# Ground_Station_2019-2020.net
KiCad netlist of a schematic drawn in EAGLE
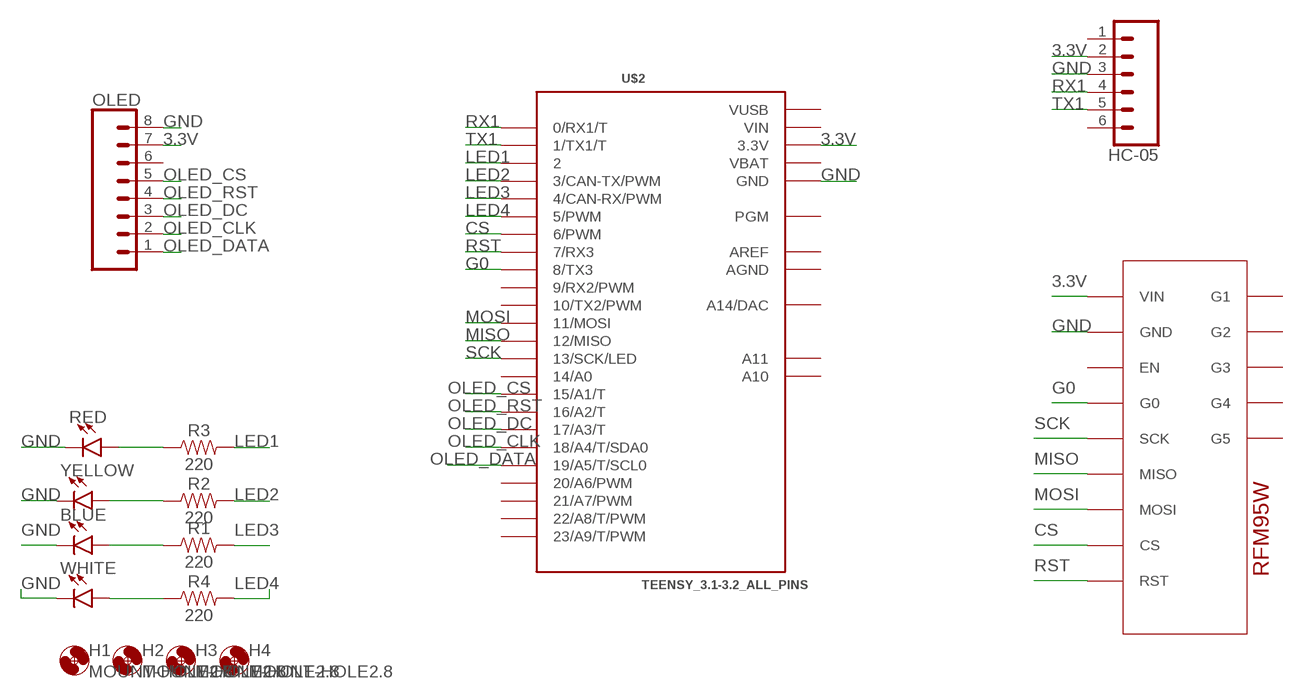
[diagram p0: schematic, sheet 1]

(export (version "E")
  (design (tool "Eeschema 10.0.6"))
  (components
    (comp (ref "BLUE")
      (value "LED5MM")
      (footprint "eagle-import:LED_5MM")
      (libsource (lib "eagle-import") (part "LED5MM"))
    )
    (comp (ref "H1")
      (value "MOUNT-HOLE2.8")
      (footprint "eagle-import:2,8")
      (libsource (lib "eagle-import") (part "MOUNT-HOLE2.8"))
    )
    (comp (ref "H2")
      (value "MOUNT-HOLE2.8")
      (footprint "eagle-import:2,8")
      (libsource (lib "eagle-import") (part "MOUNT-HOLE2.8"))
    )
    (comp (ref "H3")
      (value "MOUNT-HOLE2.8")
      (footprint "eagle-import:2,8")
      (libsource (lib "eagle-import") (part "MOUNT-HOLE2.8"))
    )
    (comp (ref "H4")
      (value "MOUNT-HOLE2.8")
      (footprint "eagle-import:2,8")
      (libsource (lib "eagle-import") (part "MOUNT-HOLE2.8"))
    )
    (comp (ref "HC-05")
      (value "CONN_06SILK_FEMALE_PTH")
      (footprint "eagle-import:1X06")
      (libsource (lib "eagle-import") (part "CONN_06SILK_FEMALE_PTH"))
    )
    (comp (ref "OLED")
      (value "CONN_08\"")
      (footprint "eagle-import:1X08")
      (libsource (lib "eagle-import") (part "CONN_08{dblquote}"))
    )
    (comp (ref "R1")
      (value "220")
      (footprint "eagle-import:AXIAL-0.3")
      (libsource (lib "eagle-import") (part "330OHM-HORIZ-1/10W-5%"))
    )
    (comp (ref "R2")
      (value "220")
      (footprint "eagle-import:AXIAL-0.3")
      (libsource (lib "eagle-import") (part "330OHM-HORIZ-1/10W-5%"))
    )
    (comp (ref "R3")
      (value "220")
      (footprint "eagle-import:AXIAL-0.3")
      (libsource (lib "eagle-import") (part "330OHM-HORIZ-1/10W-5%"))
    )
    (comp (ref "R4")
      (value "220")
      (footprint "eagle-import:AXIAL-0.3")
      (libsource (lib "eagle-import") (part "330OHM-HORIZ-1/10W-5%"))
    )
    (comp (ref "RED")
      (value "LED5MM")
      (footprint "eagle-import:LED_5MM")
      (libsource (lib "eagle-import") (part "LED5MM"))
    )
    (comp (ref "U$2")
      (value "TEENSY_3.1-3.2_ALL_PINS")
      (footprint "eagle-import:TEENSY_3.0-3.2&LC_ALL_PINS")
      (libsource (lib "eagle-import") (part "TEENSY_3.1-3.2_ALL_PINS"))
    )
    (comp (ref "U1")
      (value "ADAFRUIT_RFM95W_LORA_RADIO")
      (footprint "eagle-import:ADAFRUIT_RFM95W_LORA_RADIO")
      (libsource (lib "eagle-import") (part "ADAFRUIT_RFM95W_LORA_RADIO"))
    )
    (comp (ref "WHITE")
      (value "LED5MM")
      (footprint "eagle-import:LED_5MM")
      (libsource (lib "eagle-import") (part "LED5MM"))
    )
    (comp (ref "YELLOW")
      (value "LED5MM")
      (footprint "eagle-import:LED_5MM")
      (libsource (lib "eagle-import") (part "LED5MM"))
    )
  )
  (nets
    (net (code "1") (name "/3.3V") (class "Default")
      (node (ref "HC-05") (pin "2") (pinfunction "2_2") (pintype "passive"))
      (node (ref "OLED") (pin "7") (pinfunction "7_7") (pintype "passive"))
      (node (ref "U$2") (pin "3.3V") (pinfunction "3.3V_3.3V") (pintype "power_in"))
      (node (ref "U$2") (pin "3.3V1") (pinfunction "3.3V_3.3V1") (pintype "power_in"))
      (node (ref "U1") (pin "1") (pinfunction "VIN_1") (pintype "bidirectional"))
    )
    (net (code "2") (name "/AGND") (class "Default")
      (node (ref "U$2") (pin "AGND") (pinfunction "AGND_AGND") (pintype "power_in"))
    )
    (net (code "3") (name "/AREF") (class "Default")
      (node (ref "U$2") (pin "AREF") (pinfunction "AREF_AREF") (pintype "power_in"))
    )
    (net (code "4") (name "/CS") (class "Default")
      (node (ref "U$2") (pin "6") (pinfunction "6/PWM_6") (pintype "bidirectional"))
      (node (ref "U1") (pin "8") (pinfunction "CS_8") (pintype "bidirectional"))
    )
    (net (code "5") (name "/G0") (class "Default")
      (node (ref "U$2") (pin "8") (pinfunction "8/TX3_8") (pintype "bidirectional"))
      (node (ref "U1") (pin "4") (pinfunction "G0_4") (pintype "bidirectional"))
    )
    (net (code "6") (name "/GND") (class "Default")
      (node (ref "BLUE") (pin "K") (pinfunction "C_K") (pintype "passive"))
      (node (ref "HC-05") (pin "3") (pinfunction "3_3") (pintype "passive"))
      (node (ref "OLED") (pin "8") (pinfunction "8_8") (pintype "passive"))
      (node (ref "RED") (pin "K") (pinfunction "C_K") (pintype "passive"))
      (node (ref "U$2") (pin "GND") (pinfunction "GND_GND") (pintype "power_in"))
      (node (ref "U$2") (pin "GND1") (pinfunction "GND_GND1") (pintype "power_in"))
      (node (ref "U1") (pin "2") (pinfunction "GND_2") (pintype "bidirectional"))
      (node (ref "WHITE") (pin "K") (pinfunction "C_K") (pintype "passive"))
      (node (ref "YELLOW") (pin "K") (pinfunction "C_K") (pintype "passive"))
    )
    (net (code "7") (name "/LED1") (class "Default")
      (node (ref "R3") (pin "P$2") (pinfunction "2_P$2") (pintype "passive"))
      (node (ref "U$2") (pin "2") (pinfunction "2_2") (pintype "bidirectional"))
    )
    (net (code "8") (name "/LED2") (class "Default")
      (node (ref "R2") (pin "P$2") (pinfunction "2_P$2") (pintype "passive"))
      (node (ref "U$2") (pin "3") (pinfunction "3/CAN-TX/PWM_3") (pintype "bidirectional"))
    )
    (net (code "9") (name "/LED3") (class "Default")
      (node (ref "R1") (pin "P$2") (pinfunction "2_P$2") (pintype "passive"))
      (node (ref "U$2") (pin "4") (pinfunction "4/CAN-RX/PWM_4") (pintype "bidirectional"))
    )
    (net (code "10") (name "/LED4") (class "Default")
      (node (ref "R4") (pin "P$2") (pinfunction "2_P$2") (pintype "passive"))
      (node (ref "U$2") (pin "5") (pinfunction "5/PWM_5") (pintype "bidirectional"))
    )
    (net (code "11") (name "/MISO") (class "Default")
      (node (ref "U$2") (pin "12") (pinfunction "12/MISO_12") (pintype "bidirectional"))
      (node (ref "U1") (pin "6") (pinfunction "MISO_6") (pintype "bidirectional"))
    )
    (net (code "12") (name "/MOSI") (class "Default")
      (node (ref "U$2") (pin "11") (pinfunction "11/MOSI_11") (pintype "bidirectional"))
      (node (ref "U1") (pin "7") (pinfunction "MOSI_7") (pintype "bidirectional"))
    )
    (net (code "13") (name "/OLED_CLK") (class "Default")
      (node (ref "OLED") (pin "2") (pinfunction "2_2") (pintype "passive"))
      (node (ref "U$2") (pin "18/A4") (pinfunction "18/A4/T/SDA0_18/A4") (pintype "bidirectional"))
    )
    (net (code "14") (name "/OLED_CS") (class "Default")
      (node (ref "OLED") (pin "5") (pinfunction "5_5") (pintype "passive"))
      (node (ref "U$2") (pin "15/A1") (pinfunction "15/A1/T_15/A1") (pintype "bidirectional"))
    )
    (net (code "15") (name "/OLED_DATA") (class "Default")
      (node (ref "OLED") (pin "1") (pinfunction "1_1") (pintype "passive"))
      (node (ref "U$2") (pin "19/A5") (pinfunction "19/A5/T/SCL0_19/A5") (pintype "bidirectional"))
    )
    (net (code "16") (name "/OLED_DC") (class "Default")
      (node (ref "OLED") (pin "3") (pinfunction "3_3") (pintype "passive"))
      (node (ref "U$2") (pin "17/A3") (pinfunction "17/A3/T_17/A3") (pintype "bidirectional"))
    )
    (net (code "17") (name "/OLED_RST") (class "Default")
      (node (ref "OLED") (pin "4") (pinfunction "4_4") (pintype "passive"))
      (node (ref "U$2") (pin "16/A2") (pinfunction "16/A2/T_16/A2") (pintype "bidirectional"))
    )
    (net (code "18") (name "/RST") (class "Default")
      (node (ref "U$2") (pin "7") (pinfunction "7/RX3_7") (pintype "bidirectional"))
      (node (ref "U1") (pin "9") (pinfunction "RST_9") (pintype "bidirectional"))
    )
    (net (code "19") (name "/RX1") (class "Default")
      (node (ref "HC-05") (pin "4") (pinfunction "4_4") (pintype "passive"))
      (node (ref "U$2") (pin "0") (pinfunction "0/RX1/T_0") (pintype "bidirectional"))
    )
    (net (code "20") (name "/SCK") (class "Default")
      (node (ref "U$2") (pin "13") (pinfunction "13/SCK/LED_13") (pintype "bidirectional"))
      (node (ref "U1") (pin "5") (pinfunction "SCK_5") (pintype "bidirectional"))
    )
    (net (code "21") (name "/TX1") (class "Default")
      (node (ref "HC-05") (pin "5") (pinfunction "5_5") (pintype "passive"))
      (node (ref "U$2") (pin "1") (pinfunction "1/TX1/T_1") (pintype "bidirectional"))
    )
    (net (code "22") (name "/VBAT") (class "Default")
      (node (ref "U$2") (pin "VBAT") (pinfunction "VBAT_VBAT") (pintype "power_in"))
    )
    (net (code "23") (name "/VIN") (class "Default")
      (node (ref "U$2") (pin "VIN") (pinfunction "VIN_VIN") (pintype "power_in"))
    )
    (net (code "24") (name "/VUSB") (class "Default")
      (node (ref "U$2") (pin "VUSB") (pinfunction "VUSB_VUSB") (pintype "power_in"))
    )
    (net (code "25") (name "Net-(R1-1)") (class "Default")
      (node (ref "BLUE") (pin "A") (pinfunction "A_A") (pintype "passive"))
      (node (ref "R1") (pin "P$1") (pinfunction "1_P$1") (pintype "passive"))
    )
    (net (code "26") (name "Net-(R2-1)") (class "Default")
      (node (ref "R2") (pin "P$1") (pinfunction "1_P$1") (pintype "passive"))
      (node (ref "YELLOW") (pin "A") (pinfunction "A_A") (pintype "passive"))
    )
    (net (code "27") (name "Net-(R3-1)") (class "Default")
      (node (ref "R3") (pin "P$1") (pinfunction "1_P$1") (pintype "passive"))
      (node (ref "RED") (pin "A") (pinfunction "A_A") (pintype "passive"))
    )
    (net (code "28") (name "Net-(R4-1)") (class "Default")
      (node (ref "R4") (pin "P$1") (pinfunction "1_P$1") (pintype "passive"))
      (node (ref "WHITE") (pin "A") (pinfunction "A_A") (pintype "passive"))
    )
    (net (code "29") (name "unconnected-(HC-05-Pad1)") (class "Default")
      (node (ref "HC-05") (pin "1") (pinfunction "1_1") (pintype "passive"))
    )
    (net (code "30") (name "unconnected-(HC-05-Pad6)") (class "Default")
      (node (ref "HC-05") (pin "6") (pinfunction "6_6") (pintype "passive"))
    )
    (net (code "31") (name "unconnected-(OLED-Pad6)") (class "Default")
      (node (ref "OLED") (pin "6") (pinfunction "6_6") (pintype "passive"))
    )
    (net (code "32") (name "unconnected-(U$2-9{slash}RX2{slash}PWM-Pad9)") (class "Default")
      (node (ref "U$2") (pin "9") (pinfunction "9/RX2/PWM_9") (pintype "bidirectional"))
    )
    (net (code "33") (name "unconnected-(U$2-10{slash}TX2{slash}PWM-Pad10)") (class "Default")
      (node (ref "U$2") (pin "10") (pinfunction "10/TX2/PWM_10") (pintype "bidirectional"))
    )
    (net (code "34") (name "unconnected-(U$2-20{slash}A6{slash}PWM-Pad20{slash}A6)") (class "Default")
      (node (ref "U$2") (pin "20/A6") (pinfunction "20/A6/PWM_20/A6") (pintype "bidirectional"))
    )
    (net (code "35") (name "unconnected-(U$2-21{slash}A7{slash}PWM-Pad21{slash}A7)") (class "Default")
      (node (ref "U$2") (pin "21/A7") (pinfunction "21/A7/PWM_21/A7") (pintype "bidirectional"))
    )
    (net (code "36") (name "unconnected-(U$2-22{slash}A8{slash}T{slash}PWM-Pad22{slash}A8)") (class "Default")
      (node (ref "U$2") (pin "22/A8") (pinfunction "22/A8/T/PWM_22/A8") (pintype "bidirectional"))
    )
    (net (code "37") (name "unconnected-(U$2-23{slash}A9{slash}T{slash}PWM-Pad23{slash}A9)") (class "Default")
      (node (ref "U$2") (pin "23/A9") (pinfunction "23/A9/T/PWM_23/A9") (pintype "bidirectional"))
    )
    (net (code "38") (name "unconnected-(U$2-A14{slash}DAC-PadRESET{slash}DAC)") (class "Default")
      (node (ref "U$2") (pin "RESET/DAC") (pinfunction "A14/DAC_RESET/DAC") (pintype "bidirectional"))
    )
    (net (code "39") (name "unconnected-(U$2-Pad14{slash}A0)") (class "Default")
      (node (ref "U$2") (pin "14/A0") (pinfunction "14/A0_14/A0") (pintype "bidirectional"))
    )
    (net (code "40") (name "unconnected-(U$2-PadA10)") (class "Default")
      (node (ref "U$2") (pin "A10") (pinfunction "A10_A10") (pintype "bidirectional"))
    )
    (net (code "41") (name "unconnected-(U$2-PadA11)") (class "Default")
      (node (ref "U$2") (pin "A11") (pinfunction "A11_A11") (pintype "bidirectional"))
    )
    (net (code "42") (name "unconnected-(U$2-PadPGM)") (class "Default")
      (node (ref "U$2") (pin "PGM") (pinfunction "PGM_PGM") (pintype "bidirectional"))
    )
    (net (code "43") (name "unconnected-(U1-EN-Pad3)") (class "Default")
      (node (ref "U1") (pin "3") (pinfunction "EN_3") (pintype "bidirectional"))
    )
    (net (code "44") (name "unconnected-(U1-G1-Pad10)") (class "Default")
      (node (ref "U1") (pin "10") (pinfunction "G1_10") (pintype "bidirectional"))
    )
    (net (code "45") (name "unconnected-(U1-G2-Pad11)") (class "Default")
      (node (ref "U1") (pin "11") (pinfunction "G2_11") (pintype "bidirectional"))
    )
    (net (code "46") (name "unconnected-(U1-G3-Pad12)") (class "Default")
      (node (ref "U1") (pin "12") (pinfunction "G3_12") (pintype "bidirectional"))
    )
    (net (code "47") (name "unconnected-(U1-G4-Pad13)") (class "Default")
      (node (ref "U1") (pin "13") (pinfunction "G4_13") (pintype "bidirectional"))
    )
    (net (code "48") (name "unconnected-(U1-G5-Pad14)") (class "Default")
      (node (ref "U1") (pin "14") (pinfunction "G5_14") (pintype "bidirectional"))
    )
  )
)
